# Base.net
KiCad netlist of a schematic drawn in EAGLE
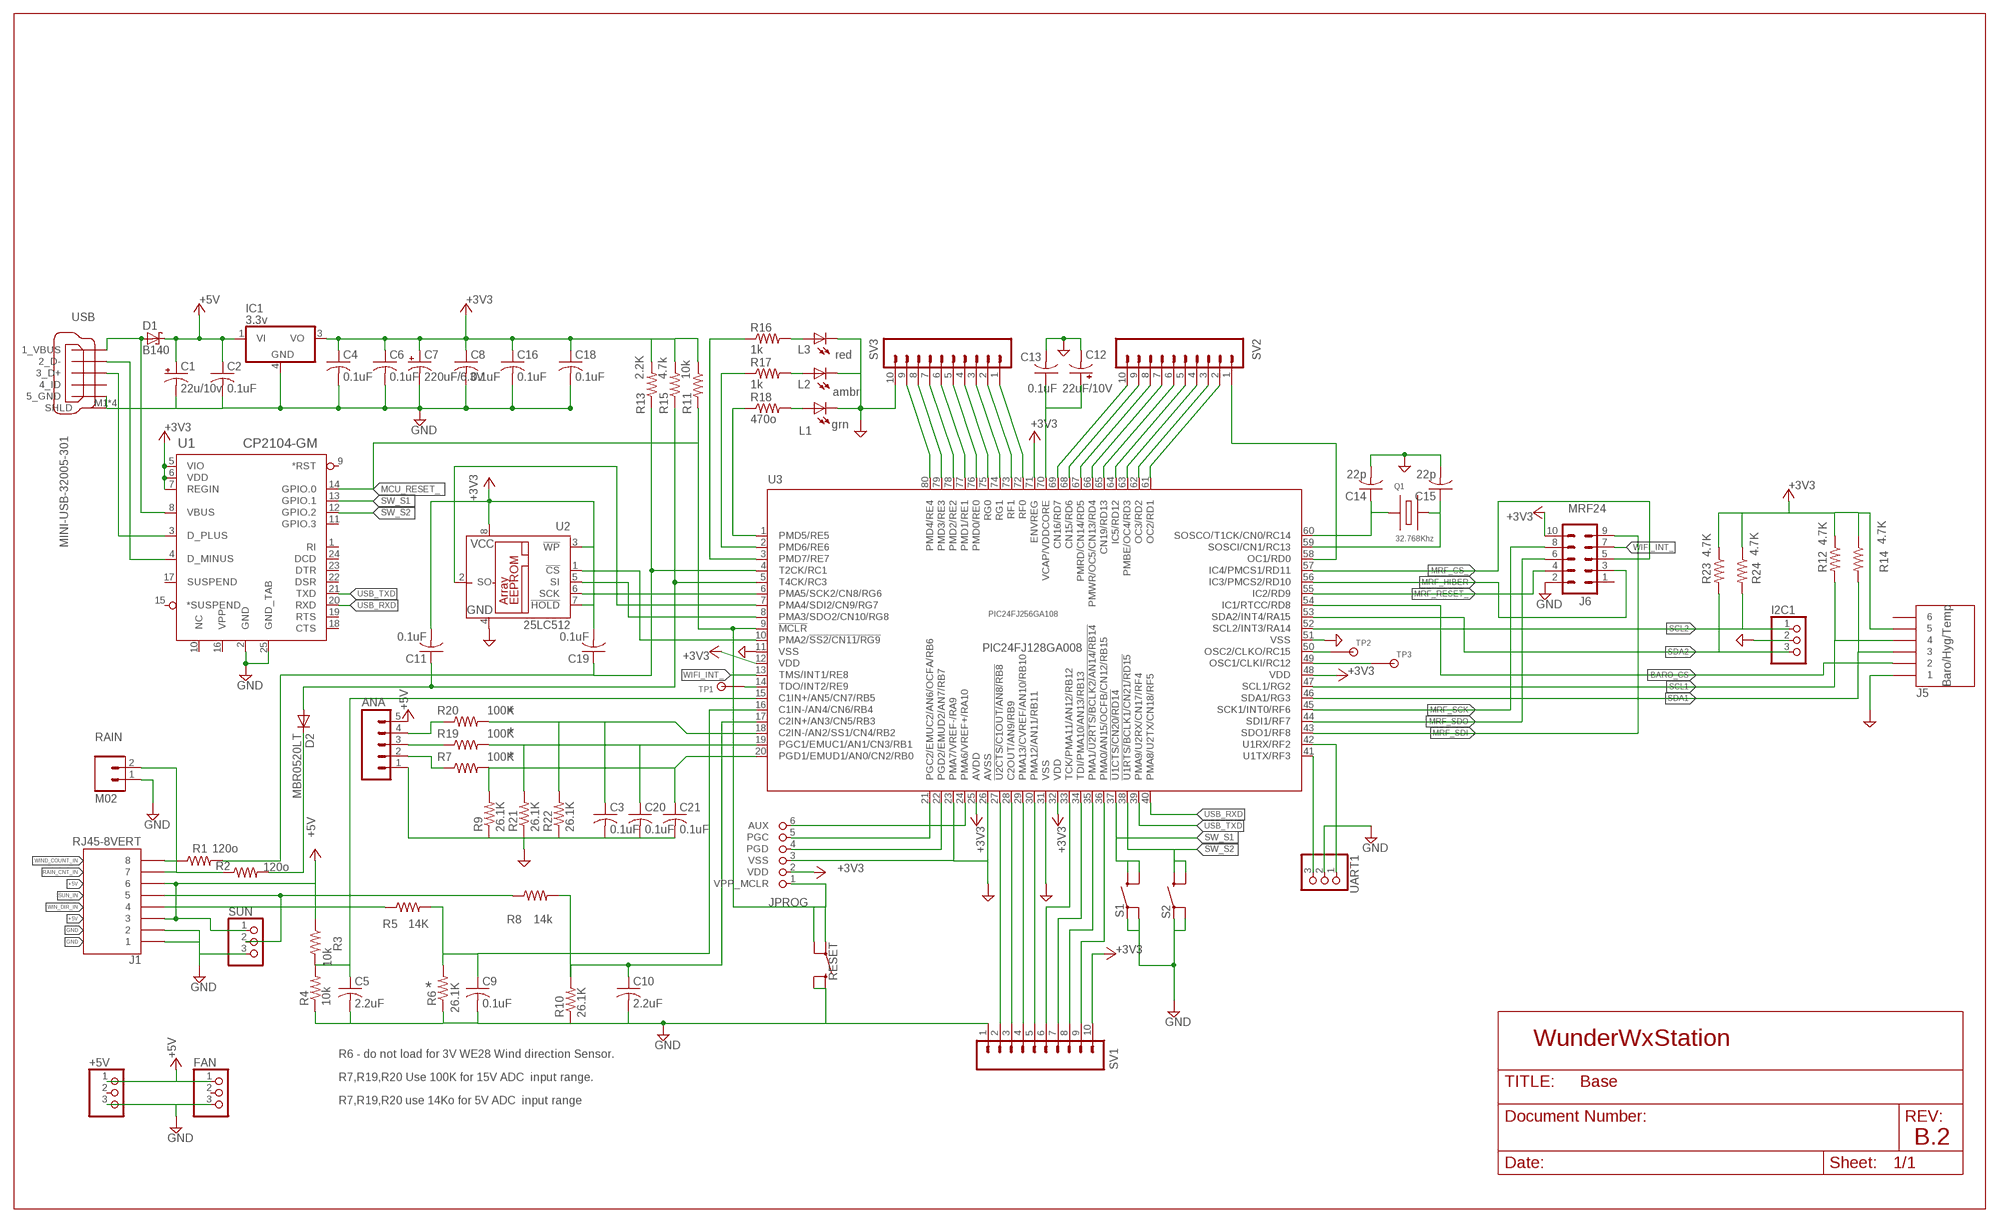
[diagram p0: schematic, sheet 1]

(export (version "E")
  (design (tool "Eeschema 10.0.6"))
  (components
    (comp (ref "+5V")
      (value "PINHD-1X3MOLEX_KK")
      (footprint "eagle-import:1X3_MOLEX_KK")
      (libsource (lib "eagle-import") (part "PINHD-1X3MOLEX_KK"))
    )
    (comp (ref "ANA")
      (value "M05PTH")
      (footprint "eagle-import:1X05")
      (libsource (lib "eagle-import") (part "M05PTH"))
    )
    (comp (ref "C1")
      (value "22u/10v")
      (footprint "eagle-import:SMC_B")
      (libsource (lib "eagle-import") (part "CPOL-USSMCB"))
    )
    (comp (ref "C2")
      (value "0.1uF")
      (footprint "eagle-import:C0805")
      (libsource (lib "eagle-import") (part "C-USC0805"))
    )
    (comp (ref "C3")
      (value "0.1uF")
      (footprint "eagle-import:C0805")
      (libsource (lib "eagle-import") (part "C-USC0805"))
    )
    (comp (ref "C4")
      (value "0.1uF")
      (footprint "eagle-import:C0805")
      (libsource (lib "eagle-import") (part "C-USC0805"))
    )
    (comp (ref "C5")
      (value "2.2uF")
      (footprint "eagle-import:C0805")
      (libsource (lib "eagle-import") (part "C-USC0805"))
    )
    (comp (ref "C6")
      (value "0.1uF")
      (footprint "eagle-import:C0805")
      (libsource (lib "eagle-import") (part "C-USC0805"))
    )
    (comp (ref "C7")
      (value "220uF/6.3V")
      (footprint "eagle-import:SMC_D")
      (libsource (lib "eagle-import") (part "CPOL-USSMCD"))
    )
    (comp (ref "C8")
      (value "0.1uF")
      (footprint "eagle-import:C0805")
      (libsource (lib "eagle-import") (part "C-USC0805"))
    )
    (comp (ref "C9")
      (value "0.1uF")
      (footprint "eagle-import:C0805")
      (libsource (lib "eagle-import") (part "C-USC0805"))
    )
    (comp (ref "C10")
      (value "2.2uF")
      (footprint "eagle-import:C0805")
      (libsource (lib "eagle-import") (part "C-USC0805"))
    )
    (comp (ref "C11")
      (value "0.1uF")
      (footprint "eagle-import:C0805")
      (libsource (lib "eagle-import") (part "C-USC0805"))
    )
    (comp (ref "C12")
      (value "22uF/10V")
      (footprint "eagle-import:SMC_B")
      (libsource (lib "eagle-import") (part "CPOL-USSMCB"))
    )
    (comp (ref "C13")
      (value "0.1uF")
      (footprint "eagle-import:C0805")
      (libsource (lib "eagle-import") (part "C-USC0805"))
    )
    (comp (ref "C14")
      (value "22p")
      (footprint "eagle-import:C0603")
      (libsource (lib "eagle-import") (part "C-USC0603"))
    )
    (comp (ref "C15")
      (value "22p")
      (footprint "eagle-import:C0603")
      (libsource (lib "eagle-import") (part "C-USC0603"))
    )
    (comp (ref "C16")
      (value "0.1uF")
      (footprint "eagle-import:C0805")
      (libsource (lib "eagle-import") (part "C-USC0805"))
    )
    (comp (ref "C18")
      (value "0.1uF")
      (footprint "eagle-import:C0805")
      (libsource (lib "eagle-import") (part "C-USC0805"))
    )
    (comp (ref "C19")
      (value "0.1uF")
      (footprint "eagle-import:C0805")
      (libsource (lib "eagle-import") (part "C-USC0805"))
    )
    (comp (ref "C20")
      (value "0.1uF")
      (footprint "eagle-import:C0805")
      (libsource (lib "eagle-import") (part "C-USC0805"))
    )
    (comp (ref "C21")
      (value "0.1uF")
      (footprint "eagle-import:C0805")
      (libsource (lib "eagle-import") (part "C-USC0805"))
    )
    (comp (ref "D1")
      (value "B140")
      (footprint "eagle-import:SMB")
      (libsource (lib "eagle-import") (part "SCHOTTKY-DIODESMD"))
    )
    (comp (ref "D2")
      (value "MBR0520LT")
      (footprint "eagle-import:SOD123")
      (libsource (lib "eagle-import") (part "MBR0520LT"))
    )
    (comp (ref "FAN")
      (value "PINHD-1X3MOLEX_KK")
      (footprint "eagle-import:1X3_MOLEX_KK")
      (libsource (lib "eagle-import") (part "PINHD-1X3MOLEX_KK"))
    )
    (comp (ref "I2C1")
      (value "PINHD-1X3")
      (footprint "eagle-import:1X03")
      (libsource (lib "eagle-import") (part "PINHD-1X3"))
    )
    (comp (ref "IC1")
      (value "3.3v")
      (footprint "eagle-import:DPACK")
      (libsource (lib "eagle-import") (part "78MXXL"))
    )
    (comp (ref "J1")
      (value "RJ45-8VERT")
      (footprint "eagle-import:RJ45_VERT")
      (libsource (lib "eagle-import") (part "RJ45-8VERT"))
    )
    (comp (ref "J5")
      (value "RJ11-6VERT_LP")
      (footprint "eagle-import:RJ11-6-VERT")
      (libsource (lib "eagle-import") (part "RJ11-6VERT_LP"))
    )
    (comp (ref "J6")
      (value "M05X22X5FE")
      (footprint "eagle-import:2X5FEMALE")
      (libsource (lib "eagle-import") (part "M05X22X5FE"))
    )
    (comp (ref "JPROG")
      (value "PIKIT2_PRG")
      (footprint "eagle-import:1X06_PIKIT")
      (libsource (lib "eagle-import") (part "PIKIT2_PRG"))
    )
    (comp (ref "L1")
      (value "grn")
      (footprint "eagle-import:CHIP-LED0603")
      (libsource (lib "eagle-import") (part "LEDCHIP-LED0603"))
    )
    (comp (ref "L2")
      (value "ambr")
      (footprint "eagle-import:CHIP-LED0603")
      (libsource (lib "eagle-import") (part "LEDCHIP-LED0603"))
    )
    (comp (ref "L3")
      (value "red")
      (footprint "eagle-import:CHIP-LED0603")
      (libsource (lib "eagle-import") (part "LEDCHIP-LED0603"))
    )
    (comp (ref "Q1")
      (value "32.768Khz")
      (footprint "eagle-import:CRYSTAL32_SMT")
      (libsource (lib "eagle-import") (part "CRYSTAL"))
    )
    (comp (ref "R1")
      (value "120o")
      (footprint "eagle-import:R0603")
      (libsource (lib "eagle-import") (part "R-US_R0603"))
    )
    (comp (ref "R2")
      (value "120o")
      (footprint "eagle-import:R0603")
      (libsource (lib "eagle-import") (part "R-US_R0603"))
    )
    (comp (ref "R3")
      (value "10k")
      (footprint "eagle-import:R0603")
      (libsource (lib "eagle-import") (part "R-US_R0603"))
    )
    (comp (ref "R4")
      (value "10k")
      (footprint "eagle-import:R0603")
      (libsource (lib "eagle-import") (part "R-US_R0603"))
    )
    (comp (ref "R5")
      (value "14K")
      (footprint "eagle-import:R0603")
      (libsource (lib "eagle-import") (part "R-US_R0603"))
    )
    (comp (ref "R6")
      (value "26.1K")
      (footprint "eagle-import:R0603")
      (libsource (lib "eagle-import") (part "R-US_R0603"))
    )
    (comp (ref "R7")
      (value "100K")
      (footprint "eagle-import:R0603")
      (libsource (lib "eagle-import") (part "R-US_R0603"))
    )
    (comp (ref "R8")
      (value "14k")
      (footprint "eagle-import:R0603")
      (libsource (lib "eagle-import") (part "R-US_R0603"))
    )
    (comp (ref "R9")
      (value "26.1K")
      (footprint "eagle-import:R0603")
      (libsource (lib "eagle-import") (part "R-US_R0603"))
    )
    (comp (ref "R10")
      (value "26.1K")
      (footprint "eagle-import:R0603")
      (libsource (lib "eagle-import") (part "R-US_R0603"))
    )
    (comp (ref "R11")
      (value "10k")
      (footprint "eagle-import:R0603")
      (libsource (lib "eagle-import") (part "R-US_R0603"))
    )
    (comp (ref "R12")
      (value "4.7K")
      (footprint "eagle-import:R0603")
      (libsource (lib "eagle-import") (part "R-US_R0603"))
    )
    (comp (ref "R13")
      (value "2.2K")
      (footprint "eagle-import:R0603")
      (libsource (lib "eagle-import") (part "R-US_R0603"))
    )
    (comp (ref "R14")
      (value "4.7K")
      (footprint "eagle-import:R0603")
      (libsource (lib "eagle-import") (part "R-US_R0603"))
    )
    (comp (ref "R15")
      (value "4.7k")
      (footprint "eagle-import:R0603")
      (libsource (lib "eagle-import") (part "R-US_R0603"))
    )
    (comp (ref "R16")
      (value "1k")
      (footprint "eagle-import:R0603")
      (libsource (lib "eagle-import") (part "R-US_R0603"))
    )
    (comp (ref "R17")
      (value "1k")
      (footprint "eagle-import:R0603")
      (libsource (lib "eagle-import") (part "R-US_R0603"))
    )
    (comp (ref "R18")
      (value "470o")
      (footprint "eagle-import:R0603")
      (libsource (lib "eagle-import") (part "R-US_R0603"))
    )
    (comp (ref "R19")
      (value "100K")
      (footprint "eagle-import:R0603")
      (libsource (lib "eagle-import") (part "R-US_R0603"))
    )
    (comp (ref "R20")
      (value "100K")
      (footprint "eagle-import:R0603")
      (libsource (lib "eagle-import") (part "R-US_R0603"))
    )
    (comp (ref "R21")
      (value "26.1K")
      (footprint "eagle-import:R0603")
      (libsource (lib "eagle-import") (part "R-US_R0603"))
    )
    (comp (ref "R22")
      (value "26.1K")
      (footprint "eagle-import:R0603")
      (libsource (lib "eagle-import") (part "R-US_R0603"))
    )
    (comp (ref "R23")
      (value "4.7K")
      (footprint "eagle-import:R0603")
      (libsource (lib "eagle-import") (part "R-US_R0603"))
    )
    (comp (ref "R24")
      (value "4.7K")
      (footprint "eagle-import:R0603")
      (libsource (lib "eagle-import") (part "R-US_R0603"))
    )
    (comp (ref "RAIN")
      (value "M02")
      (footprint "eagle-import:1X02")
      (libsource (lib "eagle-import") (part "M02"))
    )
    (comp (ref "RESET")
      (value "SWITCH-MOMENTARY-2SMD")
      (footprint "eagle-import:TACTILE_SWITCH_SMD")
      (libsource (lib "eagle-import") (part "SWITCH-MOMENTARY-2SMD"))
    )
    (comp (ref "S1")
      (value "SWITCH-MOMENTARY-2SMD")
      (footprint "eagle-import:TACTILE_SWITCH_SMD")
      (libsource (lib "eagle-import") (part "SWITCH-MOMENTARY-2SMD"))
    )
    (comp (ref "S2")
      (value "SWITCH-MOMENTARY-2SMD")
      (footprint "eagle-import:TACTILE_SWITCH_SMD")
      (libsource (lib "eagle-import") (part "SWITCH-MOMENTARY-2SMD"))
    )
    (comp (ref "SUN")
      (value "PINHD-1X3MOLEX_KK")
      (footprint "eagle-import:1X3_MOLEX_KK")
      (libsource (lib "eagle-import") (part "PINHD-1X3MOLEX_KK"))
    )
    (comp (ref "SV1")
      (value "M10\"")
      (footprint "eagle-import:1X10")
      (libsource (lib "eagle-import") (part "M10{dblquote}"))
    )
    (comp (ref "SV2")
      (value "M10\"")
      (footprint "eagle-import:1X10")
      (libsource (lib "eagle-import") (part "M10{dblquote}"))
    )
    (comp (ref "SV3")
      (value "M10\"")
      (footprint "eagle-import:1X10")
      (libsource (lib "eagle-import") (part "M10{dblquote}"))
    )
    (comp (ref "TP1")
      (value "TP10R")
      (footprint "eagle-import:TP10R")
      (libsource (lib "eagle-import") (part "TP10R"))
    )
    (comp (ref "TP2")
      (value "TP6R")
      (footprint "eagle-import:TP06R")
      (libsource (lib "eagle-import") (part "TP6R"))
    )
    (comp (ref "TP3")
      (value "TP6R")
      (footprint "eagle-import:TP06R")
      (libsource (lib "eagle-import") (part "TP6R"))
    )
    (comp (ref "U1")
      (value "CP2104-GM")
      (footprint "eagle-import:QFN24_4X4")
      (libsource (lib "eagle-import") (part "CP2104-GM"))
    )
    (comp (ref "U2")
      (value "25LC512")
      (footprint "eagle-import:SO-08")
      (fields (field (name "MF") "MICROCHIP") (field (name "MPN") "25LC080/SN"))
      (libsource (lib "eagle-import") (part "25SNLC080"))
    )
    (comp (ref "U3")
      (value "PIC24FJ128GA008")
      (footprint "eagle-import:TQFP80-12X12")
      (fields (field (name "MF") "MICROCHIP") (field (name "MPN") "PIC24FJ128GA008-I/PT"))
      (libsource (lib "eagle-import") (part "PIC24FJGA008128"))
    )
    (comp (ref "UART1")
      (value "PINHD-1X3")
      (footprint "eagle-import:1X03")
      (libsource (lib "eagle-import") (part "PINHD-1X3"))
    )
    (comp (ref "USB")
      (value "MINI-USB-32005-301")
      (footprint "eagle-import:32005-301")
      (libsource (lib "eagle-import") (part "MINI-USB-32005-301"))
    )
  )
  (nets
    (net (code "1") (name "+3V3") (class "Default")
      (node (ref "C11") (pin "2") (pinfunction "2_2") (pintype "passive"))
      (node (ref "C16") (pin "1") (pinfunction "1_1") (pintype "passive"))
      (node (ref "C18") (pin "1") (pinfunction "1_1") (pintype "passive"))
      (node (ref "C19") (pin "2") (pinfunction "2_2") (pintype "passive"))
      (node (ref "C4") (pin "1") (pinfunction "1_1") (pintype "passive"))
      (node (ref "C6") (pin "1") (pinfunction "1_1") (pintype "passive"))
      (node (ref "C7") (pin "+") (pinfunction "+_+") (pintype "passive"))
      (node (ref "C8") (pin "1") (pinfunction "1_1") (pintype "passive"))
      (node (ref "IC1") (pin "3") (pinfunction "VO_3") (pintype "passive"))
      (node (ref "J5") (pin "P$5") (pinfunction "5_P$5") (pintype "bidirectional"))
      (node (ref "J6") (pin "10") (pinfunction "10_10") (pintype "passive"))
      (node (ref "JPROG") (pin "2") (pinfunction "VDD_2") (pintype "passive"))
      (node (ref "R11") (pin "1") (pinfunction "1_1") (pintype "passive"))
      (node (ref "R12") (pin "1") (pinfunction "1_1") (pintype "passive"))
      (node (ref "R13") (pin "2") (pinfunction "2_2") (pintype "passive"))
      (node (ref "R14") (pin "1") (pinfunction "1_1") (pintype "passive"))
      (node (ref "R15") (pin "2") (pinfunction "2_2") (pintype "passive"))
      (node (ref "R23") (pin "1") (pinfunction "1_1") (pintype "passive"))
      (node (ref "R24") (pin "1") (pinfunction "1_1") (pintype "passive"))
      (node (ref "SV1") (pin "10") (pinfunction "10_10") (pintype "passive"))
      (node (ref "U1") (pin "5") (pinfunction "VIO_5") (pintype "power_in"))
      (node (ref "U1") (pin "6") (pinfunction "VDD_6") (pintype "power_in"))
      (node (ref "U1") (pin "7") (pinfunction "REGIN_7") (pintype "input"))
      (node (ref "U2") (pin "3") (pinfunction "~{WP}_3") (pintype "input"))
      (node (ref "U2") (pin "7") (pinfunction "~{HOLD}_7") (pintype "input"))
      (node (ref "U2") (pin "8") (pinfunction "VCC_8") (pintype "power_in"))
      (node (ref "U3") (pin "12") (pinfunction "VDD_12") (pintype "power_in"))
      (node (ref "U3") (pin "25") (pinfunction "AVDD_25") (pintype "power_in"))
      (node (ref "U3") (pin "32") (pinfunction "VDD_32") (pintype "power_in"))
      (node (ref "U3") (pin "48") (pinfunction "VDD_48") (pintype "power_in"))
      (node (ref "U3") (pin "71") (pinfunction "ENVREG_71") (pintype "bidirectional"))
    )
    (net (code "2") (name "+5V") (class "Default")
      (node (ref "+5V") (pin "1") (pinfunction "1_1") (pintype "passive"))
      (node (ref "ANA") (pin "5") (pinfunction "5_5") (pintype "passive"))
      (node (ref "C1") (pin "+") (pinfunction "+_+") (pintype "passive"))
      (node (ref "C2") (pin "1") (pinfunction "1_1") (pintype "passive"))
      (node (ref "D1") (pin "C") (pinfunction "C_C") (pintype "passive"))
      (node (ref "FAN") (pin "1") (pinfunction "1_1") (pintype "passive"))
      (node (ref "IC1") (pin "1") (pinfunction "VI_1") (pintype "input"))
      (node (ref "J1") (pin "P$3") (pinfunction "3_P$3") (pintype "bidirectional"))
      (node (ref "J1") (pin "P$6") (pinfunction "6_P$6") (pintype "bidirectional"))
      (node (ref "R3") (pin "1") (pinfunction "1_1") (pintype "passive"))
      (node (ref "SUN") (pin "1") (pinfunction "1_1") (pintype "passive"))
    )
    (net (code "3") (name "BARO_CS") (class "Default")
      (node (ref "J5") (pin "P$2") (pinfunction "2_P$2") (pintype "bidirectional"))
      (node (ref "U3") (pin "54") (pinfunction "IC1/RTCC/RD8_54") (pintype "bidirectional"))
    )
    (net (code "4") (name "GND") (class "Default")
      (node (ref "+5V") (pin "3") (pinfunction "3_3") (pintype "passive"))
      (node (ref "ANA") (pin "1") (pinfunction "1_1") (pintype "passive"))
      (node (ref "C1") (pin "-") (pinfunction "-_-") (pintype "passive"))
      (node (ref "C10") (pin "2") (pinfunction "2_2") (pintype "passive"))
      (node (ref "C12") (pin "-") (pinfunction "-_-") (pintype "passive"))
      (node (ref "C13") (pin "2") (pinfunction "2_2") (pintype "passive"))
      (node (ref "C14") (pin "2") (pinfunction "2_2") (pintype "passive"))
      (node (ref "C15") (pin "2") (pinfunction "2_2") (pintype "passive"))
      (node (ref "C16") (pin "2") (pinfunction "2_2") (pintype "passive"))
      (node (ref "C18") (pin "2") (pinfunction "2_2") (pintype "passive"))
      (node (ref "C2") (pin "2") (pinfunction "2_2") (pintype "passive"))
      (node (ref "C20") (pin "2") (pinfunction "2_2") (pintype "passive"))
      (node (ref "C21") (pin "2") (pinfunction "2_2") (pintype "passive"))
      (node (ref "C3") (pin "2") (pinfunction "2_2") (pintype "passive"))
      (node (ref "C4") (pin "2") (pinfunction "2_2") (pintype "passive"))
      (node (ref "C5") (pin "2") (pinfunction "2_2") (pintype "passive"))
      (node (ref "C6") (pin "2") (pinfunction "2_2") (pintype "passive"))
      (node (ref "C7") (pin "-") (pinfunction "-_-") (pintype "passive"))
      (node (ref "C8") (pin "2") (pinfunction "2_2") (pintype "passive"))
      (node (ref "C9") (pin "2") (pinfunction "2_2") (pintype "passive"))
      (node (ref "FAN") (pin "3") (pinfunction "3_3") (pintype "passive"))
      (node (ref "I2C1") (pin "2") (pinfunction "2_2") (pintype "passive"))
      (node (ref "IC1") (pin "4") (pinfunction "GND_4") (pintype "passive"))
      (node (ref "J1") (pin "P$1") (pinfunction "1_P$1") (pintype "bidirectional"))
      (node (ref "J1") (pin "P$2") (pinfunction "2_P$2") (pintype "bidirectional"))
      (node (ref "J5") (pin "P$1") (pinfunction "1_P$1") (pintype "bidirectional"))
      (node (ref "J6") (pin "2") (pinfunction "2_2") (pintype "passive"))
      (node (ref "JPROG") (pin "3") (pinfunction "VSS_3") (pintype "passive"))
      (node (ref "L1") (pin "C") (pinfunction "C_C") (pintype "passive"))
      (node (ref "L2") (pin "C") (pinfunction "C_C") (pintype "passive"))
      (node (ref "L3") (pin "C") (pinfunction "C_C") (pintype "passive"))
      (node (ref "R10") (pin "1") (pinfunction "1_1") (pintype "passive"))
      (node (ref "R21") (pin "1") (pinfunction "1_1") (pintype "passive"))
      (node (ref "R22") (pin "1") (pinfunction "1_1") (pintype "passive"))
      (node (ref "R4") (pin "1") (pinfunction "1_1") (pintype "passive"))
      (node (ref "R6") (pin "1") (pinfunction "1_1") (pintype "passive"))
      (node (ref "R9") (pin "1") (pinfunction "1_1") (pintype "passive"))
      (node (ref "RAIN") (pin "1") (pinfunction "1_1") (pintype "passive"))
      (node (ref "RESET") (pin "3") (pinfunction "2_3") (pintype "passive"))
      (node (ref "RESET") (pin "4") (pinfunction "3_4") (pintype "passive"))
      (node (ref "S1") (pin "1") (pinfunction "1_1") (pintype "passive"))
      (node (ref "S1") (pin "2") (pinfunction "4_2") (pintype "passive"))
      (node (ref "S2") (pin "1") (pinfunction "1_1") (pintype "passive"))
      (node (ref "S2") (pin "2") (pinfunction "4_2") (pintype "passive"))
      (node (ref "SUN") (pin "3") (pinfunction "3_3") (pintype "passive"))
      (node (ref "SV1") (pin "1") (pinfunction "1_1") (pintype "passive"))
      (node (ref "SV3") (pin "10") (pinfunction "10_10") (pintype "passive"))
      (node (ref "U1") (pin "2") (pinfunction "GND_2") (pintype "power_in"))
      (node (ref "U1") (pin "25") (pinfunction "GND_TAB_25") (pintype "passive"))
      (node (ref "U2") (pin "4") (pinfunction "GND_4") (pintype "power_in"))
      (node (ref "U3") (pin "11") (pinfunction "VSS_11") (pintype "power_in"))
      (node (ref "U3") (pin "23") (pinfunction "PMA7/VREF-/RA9_23") (pintype "bidirectional"))
      (node (ref "U3") (pin "26") (pinfunction "AVSS_26") (pintype "power_in"))
      (node (ref "U3") (pin "31") (pinfunction "VSS_31") (pintype "power_in"))
      (node (ref "U3") (pin "51") (pinfunction "VSS_51") (pintype "power_in"))
      (node (ref "UART1") (pin "2") (pinfunction "2_2") (pintype "passive"))
      (node (ref "USB") (pin "5_USB_GND") (pinfunction "5_GND_5_USB_GND") (pintype "passive"))
      (node (ref "USB") (pin "M1") (pinfunction "SHLD_M1") (pintype "passive"))
      (node (ref "USB") (pin "M2") (pinfunction "SHLD_M2") (pintype "passive"))
      (node (ref "USB") (pin "M3") (pinfunction "SHLD_M3") (pintype "passive"))
      (node (ref "USB") (pin "M4") (pinfunction "SHLD_M4") (pintype "passive"))
    )
    (net (code "5") (name "MCU_RESET_") (class "Default")
      (node (ref "JPROG") (pin "1") (pinfunction "VPP_MCLR_1") (pintype "passive"))
      (node (ref "R11") (pin "2") (pinfunction "2_2") (pintype "passive"))
      (node (ref "RESET") (pin "1") (pinfunction "1_1") (pintype "passive"))
      (node (ref "RESET") (pin "2") (pinfunction "4_2") (pintype "passive"))
      (node (ref "U1") (pin "14") (pinfunction "GPIO.0_14") (pintype "passive"))
      (node (ref "U3") (pin "9") (pinfunction "~{MCLR}_9") (pintype "bidirectional"))
    )
    (net (code "6") (name "MRF_CS_") (class "Default")
      (node (ref "J6") (pin "5") (pinfunction "5_5") (pintype "passive"))
      (node (ref "U3") (pin "57") (pinfunction "IC4/PMCS1/RD11_57") (pintype "bidirectional"))
    )
    (net (code "7") (name "MRF_HIBER") (class "Default")
      (node (ref "J6") (pin "3") (pinfunction "3_3") (pintype "passive"))
      (node (ref "U3") (pin "56") (pinfunction "IC3/PMCS2/RD10_56") (pintype "bidirectional"))
    )
    (net (code "8") (name "MRF_RESET_") (class "Default")
      (node (ref "J6") (pin "4") (pinfunction "4_4") (pintype "passive"))
      (node (ref "U3") (pin "55") (pinfunction "IC2/RD9_55") (pintype "bidirectional"))
    )
    (net (code "9") (name "MRF_SCK") (class "Default")
      (node (ref "J6") (pin "8") (pinfunction "8_8") (pintype "passive"))
      (node (ref "U3") (pin "45") (pinfunction "SCK1/INT0/RF6_45") (pintype "bidirectional"))
    )
    (net (code "10") (name "MRF_SDI") (class "Default")
      (node (ref "J6") (pin "9") (pinfunction "9_9") (pintype "passive"))
      (node (ref "U3") (pin "43") (pinfunction "SDO1/RF8_43") (pintype "bidirectional"))
    )
    (net (code "11") (name "MRF_SDO") (class "Default")
      (node (ref "J6") (pin "6") (pinfunction "6_6") (pintype "passive"))
      (node (ref "U3") (pin "44") (pinfunction "SDI1/RF7_44") (pintype "bidirectional"))
    )
    (net (code "12") (name "Net-(ANA-Pad2)") (class "Default")
      (node (ref "ANA") (pin "2") (pinfunction "2_2") (pintype "passive"))
      (node (ref "R7") (pin "1") (pinfunction "1_1") (pintype "passive"))
    )
    (net (code "13") (name "Net-(ANA-Pad3)") (class "Default")
      (node (ref "ANA") (pin "3") (pinfunction "3_3") (pintype "passive"))
      (node (ref "R19") (pin "1") (pinfunction "1_1") (pintype "passive"))
    )
    (net (code "14") (name "Net-(ANA-Pad4)") (class "Default")
      (node (ref "ANA") (pin "4") (pinfunction "4_4") (pintype "passive"))
      (node (ref "R20") (pin "1") (pinfunction "1_1") (pintype "passive"))
    )
    (net (code "15") (name "Net-(D2-PadC)") (class "Default")
      (node (ref "D2") (pin "C") (pinfunction "C_C") (pintype "passive"))
      (node (ref "R2") (pin "2") (pinfunction "2_2") (pintype "passive"))
    )
    (net (code "16") (name "Net-(JPROG-AUX)") (class "Default")
      (node (ref "JPROG") (pin "6") (pinfunction "AUX_6") (pintype "passive"))
      (node (ref "U3") (pin "24") (pinfunction "PMA6/VREF+/RA10_24") (pintype "bidirectional"))
    )
    (net (code "17") (name "Net-(JPROG-PGC)") (class "Default")
      (node (ref "JPROG") (pin "5") (pinfunction "PGC_5") (pintype "passive"))
      (node (ref "U3") (pin "21") (pinfunction "PGC2/EMUC2/AN6/OCFA/RB6_21") (pintype "bidirectional"))
    )
    (net (code "18") (name "Net-(JPROG-PGD)") (class "Default")
      (node (ref "JPROG") (pin "4") (pinfunction "PGD_4") (pintype "passive"))
      (node (ref "U3") (pin "22") (pinfunction "PGD2/EMUD2/AN7/RB7_22") (pintype "bidirectional"))
    )
    (net (code "19") (name "Net-(L1-PadA)") (class "Default")
      (node (ref "L1") (pin "A") (pinfunction "A_A") (pintype "passive"))
      (node (ref "R18") (pin "2") (pinfunction "2_2") (pintype "passive"))
    )
    (net (code "20") (name "Net-(L2-PadA)") (class "Default")
      (node (ref "L2") (pin "A") (pinfunction "A_A") (pintype "passive"))
      (node (ref "R17") (pin "2") (pinfunction "2_2") (pintype "passive"))
    )
    (net (code "21") (name "Net-(L3-PadA)") (class "Default")
      (node (ref "L3") (pin "A") (pinfunction "A_A") (pintype "passive"))
      (node (ref "R16") (pin "2") (pinfunction "2_2") (pintype "passive"))
    )
    (net (code "22") (name "Net-(Q1-P$1)") (class "Default")
      (node (ref "C14") (pin "1") (pinfunction "1_1") (pintype "passive"))
      (node (ref "Q1") (pin "P$2") (pinfunction "P$1_P$2") (pintype "bidirectional"))
      (node (ref "U3") (pin "60") (pinfunction "SOSCO/T1CK/CN0/RC14_60") (pintype "bidirectional"))
    )
    (net (code "23") (name "Net-(Q1-P$2)") (class "Default")
      (node (ref "C15") (pin "1") (pinfunction "1_1") (pintype "passive"))
      (node (ref "Q1") (pin "P$3") (pinfunction "P$2_P$3") (pintype "bidirectional"))
      (node (ref "U3") (pin "59") (pinfunction "SOSCI/CN1/RC13_59") (pintype "bidirectional"))
    )
    (net (code "24") (name "Net-(TP1-P$1)") (class "Default")
      (node (ref "TP1") (pin "TP_1") (pinfunction "P$1_TP_1") (pintype "bidirectional"))
      (node (ref "U3") (pin "14") (pinfunction "TDO/INT2/RE9_14") (pintype "bidirectional"))
    )
    (net (code "25") (name "Net-(TP2-P$1)") (class "Default")
      (node (ref "TP2") (pin "TP_1") (pinfunction "P$1_TP_1") (pintype "bidirectional"))
      (node (ref "U3") (pin "50") (pinfunction "OSC2/CLKO/RC15_50") (pintype "bidirectional"))
    )
    (net (code "26") (name "Net-(TP3-P$1)") (class "Default")
      (node (ref "TP3") (pin "TP_1") (pinfunction "P$1_TP_1") (pintype "bidirectional"))
      (node (ref "U3") (pin "49") (pinfunction "OSC1/CLKI/RC12_49") (pintype "bidirectional"))
    )
    (net (code "27") (name "Net-(U1-D_MINUS)") (class "Default")
      (node (ref "U1") (pin "4") (pinfunction "D_MINUS_4") (pintype "passive"))
      (node (ref "USB") (pin "2_D-") (pinfunction "2_D-_2_D-") (pintype "passive"))
    )
    (net (code "28") (name "Net-(U1-D_PLUS)") (class "Default")
      (node (ref "U1") (pin "3") (pinfunction "D_PLUS_3") (pintype "passive"))
      (node (ref "USB") (pin "3_D+") (pinfunction "3_D+_3_D+") (pintype "passive"))
    )
    (net (code "29") (name "Net-(U1-VBUS)") (class "Default")
      (node (ref "D1") (pin "A") (pinfunction "A_A") (pintype "passive"))
      (node (ref "U1") (pin "8") (pinfunction "VBUS_8") (pintype "input"))
      (node (ref "USB") (pin "1_VBUS") (pinfunction "1_VBUS_1_VBUS") (pintype "passive"))
    )
    (net (code "30") (name "Net-(U2-SCK)") (class "Default")
      (node (ref "U2") (pin "6") (pinfunction "SCK_6") (pintype "input"))
      (node (ref "U3") (pin "6") (pinfunction "PMA5/SCK2/CN8/RG6_6") (pintype "bidirectional"))
    )
    (net (code "31") (name "Net-(U2-SI)") (class "Default")
      (node (ref "U2") (pin "5") (pinfunction "SI_5") (pintype "input"))
      (node (ref "U3") (pin "8") (pinfunction "PMA3/SDO2/CN10/RG8_8") (pintype "bidirectional"))
    )
    (net (code "32") (name "Net-(U2-SO)") (class "Default")
      (node (ref "U2") (pin "2") (pinfunction "SO_2") (pintype "bidirectional"))
      (node (ref "U3") (pin "7") (pinfunction "PMA4/SDI2/CN9/RG7_7") (pintype "bidirectional"))
    )
    (net (code "33") (name "Net-(U2-~{CS})") (class "Default")
      (node (ref "U2") (pin "1") (pinfunction "~{CS}_1") (pintype "input"))
      (node (ref "U3") (pin "10") (pinfunction "PMA2/~{SS2/CN11/RG9}_10") (pintype "bidirectional"))
    )
    (net (code "34") (name "Net-(U3-C1IN+{slash}AN5{slash}CN7{slash}RB5)") (class "Default")
      (node (ref "C5") (pin "1") (pinfunction "1_1") (pintype "passive"))
      (node (ref "R3") (pin "2") (pinfunction "2_2") (pintype "passive"))
      (node (ref "R4") (pin "2") (pinfunction "2_2") (pintype "passive"))
      (node (ref "U3") (pin "15") (pinfunction "C1IN+/AN5/CN7/RB5_15") (pintype "bidirectional"))
    )
    (net (code "35") (name "Net-(U3-C1IN-{slash}AN4{slash}CN6{slash}RB4)") (class "Default")
      (node (ref "C9") (pin "1") (pinfunction "1_1") (pintype "passive"))
      (node (ref "R5") (pin "2") (pinfunction "2_2") (pintype "passive"))
      (node (ref "R6") (pin "2") (pinfunction "2_2") (pintype "passive"))
      (node (ref "U3") (pin "16") (pinfunction "C1IN-/AN4/CN6/RB4_16") (pintype "bidirectional"))
    )
    (net (code "36") (name "Net-(U3-C2IN+{slash}AN3{slash}CN5{slash}RB3)") (class "Default")
      (node (ref "C10") (pin "1") (pinfunction "1_1") (pintype "passive"))
      (node (ref "R10") (pin "2") (pinfunction "2_2") (pintype "passive"))
      (node (ref "R8") (pin "2") (pinfunction "2_2") (pintype "passive"))
      (node (ref "U3") (pin "17") (pinfunction "C2IN+/AN3/CN5/RB3_17") (pintype "bidirectional"))
    )
    (net (code "37") (name "Net-(U3-C2IN-{slash}AN2{slash}SS1{slash}CN4{slash}RB2)") (class "Default")
      (node (ref "C3") (pin "1") (pinfunction "1_1") (pintype "passive"))
      (node (ref "R20") (pin "2") (pinfunction "2_2") (pintype "passive"))
      (node (ref "R22") (pin "2") (pinfunction "2_2") (pintype "passive"))
      (node (ref "U3") (pin "18") (pinfunction "C2IN-/AN2/SS1/CN4/RB2_18") (pintype "bidirectional"))
    )
    (net (code "38") (name "Net-(U3-C2OUT{slash}AN9{slash}RB9)") (class "Default")
      (node (ref "SV1") (pin "3") (pinfunction "3_3") (pintype "passive"))
      (node (ref "U3") (pin "28") (pinfunction "C2OUT/AN9/RB9_28") (pintype "bidirectional"))
    )
    (net (code "39") (name "Net-(U3-CN15{slash}RD6)") (class "Default")
      (node (ref "SV2") (pin "9") (pinfunction "9_9") (pintype "passive"))
      (node (ref "U3") (pin "68") (pinfunction "CN15/RD6_68") (pintype "bidirectional"))
    )
    (net (code "40") (name "Net-(U3-CN16{slash}RD7)") (class "Default")
      (node (ref "SV2") (pin "10") (pinfunction "10_10") (pintype "passive"))
      (node (ref "U3") (pin "69") (pinfunction "CN16/RD7_69") (pintype "bidirectional"))
    )
    (net (code "41") (name "Net-(U3-CN19{slash}RD13)") (class "Default")
      (node (ref "SV2") (pin "6") (pinfunction "6_6") (pintype "passive"))
      (node (ref "U3") (pin "65") (pinfunction "CN19/RD13_65") (pintype "bidirectional"))
    )
    (net (code "42") (name "Net-(U3-IC5{slash}RD12)") (class "Default")
      (node (ref "SV2") (pin "5") (pinfunction "5_5") (pintype "passive"))
      (node (ref "U3") (pin "64") (pinfunction "IC5/RD12_64") (pintype "bidirectional"))
    )
    (net (code "43") (name "Net-(U3-OC1{slash}RD0)") (class "Default")
      (node (ref "SV2") (pin "1") (pinfunction "1_1") (pintype "passive"))
      (node (ref "U3") (pin "58") (pinfunction "OC1/RD0_58") (pintype "bidirectional"))
    )
    (net (code "44") (name "Net-(U3-OC2{slash}RD1)") (class "Default")
      (node (ref "SV2") (pin "2") (pinfunction "2_2") (pintype "passive"))
      (node (ref "U3") (pin "61") (pinfunction "OC2/RD1_61") (pintype "bidirectional"))
    )
    (net (code "45") (name "Net-(U3-OC3{slash}RD2)") (class "Default")
      (node (ref "SV2") (pin "3") (pinfunction "3_3") (pintype "passive"))
      (node (ref "U3") (pin "62") (pinfunction "OC3/RD2_62") (pintype "bidirectional"))
    )
    (net (code "46") (name "Net-(U3-PGC1{slash}EMUC1{slash}AN1{slash}CN3{slash}RB1)") (class "Default")
      (node (ref "C20") (pin "1") (pinfunction "1_1") (pintype "passive"))
      (node (ref "R19") (pin "2") (pinfunction "2_2") (pintype "passive"))
      (node (ref "R21") (pin "2") (pinfunction "2_2") (pintype "passive"))
      (node (ref "U3") (pin "19") (pinfunction "PGC1/EMUC1/AN1/CN3/RB1_19") (pintype "bidirectional"))
    )
    (net (code "47") (name "Net-(U3-PGD1{slash}EMUD1{slash}AN0{slash}CN2{slash}RB0)") (class "Default")
      (node (ref "C21") (pin "1") (pinfunction "1_1") (pintype "passive"))
      (node (ref "R7") (pin "2") (pinfunction "2_2") (pintype "passive"))
      (node (ref "R9") (pin "2") (pinfunction "2_2") (pintype "passive"))
      (node (ref "U3") (pin "20") (pinfunction "PGD1/EMUD1/AN0/CN2/RB0_20") (pintype "bidirectional"))
    )
    (net (code "48") (name "Net-(U3-PMA0{slash}AN15{slash}OCFB{slash}CN12{slash}RB15)") (class "Default")
      (node (ref "SV1") (pin "9") (pinfunction "9_9") (pintype "passive"))
      (node (ref "U3") (pin "36") (pinfunction "PMA0/AN15/OCFB/CN12/RB15_36") (pintype "bidirectional"))
    )
    (net (code "49") (name "Net-(U3-PMA1{slash}~{U2RTS{slash}BCLK2{slash}AN14{slash}RB14})") (class "Default")
      (node (ref "SV1") (pin "8") (pinfunction "8_8") (pintype "passive"))
      (node (ref "U3") (pin "35") (pinfunction "PMA1/~{U2RTS/BCLK2/AN14/RB14}_35") (pintype "bidirectional"))
    )
    (net (code "50") (name "Net-(U3-PMA12{slash}AN11{slash}RB11)") (class "Default")
      (node (ref "SV1") (pin "5") (pinfunction "5_5") (pintype "passive"))
      (node (ref "U3") (pin "30") (pinfunction "PMA12/AN11/RB11_30") (pintype "bidirectional"))
    )
    (net (code "51") (name "Net-(U3-PMA13{slash}CVREF{slash}AN10{slash}RB10)") (class "Default")
      (node (ref "SV1") (pin "4") (pinfunction "4_4") (pintype "passive"))
      (node (ref "U3") (pin "29") (pinfunction "PMA13/CVREF/AN10/RB10_29") (pintype "bidirectional"))
    )
    (net (code "52") (name "Net-(U3-PMBE{slash}OC4{slash}RD3)") (class "Default")
      (node (ref "SV2") (pin "4") (pinfunction "4_4") (pintype "passive"))
      (node (ref "U3") (pin "63") (pinfunction "PMBE/OC4/RD3_63") (pintype "bidirectional"))
    )
    (net (code "53") (name "Net-(U3-PMD0{slash}RE0)") (class "Default")
      (node (ref "SV3") (pin "5") (pinfunction "5_5") (pintype "passive"))
      (node (ref "U3") (pin "76") (pinfunction "PMD0/RE0_76") (pintype "bidirectional"))
    )
    (net (code "54") (name "Net-(U3-PMD1{slash}RE1)") (class "Default")
      (node (ref "SV3") (pin "6") (pinfunction "6_6") (pintype "passive"))
      (node (ref "U3") (pin "77") (pinfunction "PMD1/RE1_77") (pintype "bidirectional"))
    )
    (net (code "55") (name "Net-(U3-PMD2{slash}RE2)") (class "Default")
      (node (ref "SV3") (pin "7") (pinfunction "7_7") (pintype "passive"))
      (node (ref "U3") (pin "78") (pinfunction "PMD2/RE2_78") (pintype "bidirectional"))
    )
    (net (code "56") (name "Net-(U3-PMD3{slash}RE3)") (class "Default")
      (node (ref "SV3") (pin "8") (pinfunction "8_8") (pintype "passive"))
      (node (ref "U3") (pin "79") (pinfunction "PMD3/RE3_79") (pintype "bidirectional"))
    )
    (net (code "57") (name "Net-(U3-PMD4{slash}RE4)") (class "Default")
      (node (ref "SV3") (pin "9") (pinfunction "9_9") (pintype "passive"))
      (node (ref "U3") (pin "80") (pinfunction "PMD4/RE4_80") (pintype "bidirectional"))
    )
    (net (code "58") (name "Net-(U3-PMD5{slash}RE5)") (class "Default")
      (node (ref "R18") (pin "1") (pinfunction "1_1") (pintype "passive"))
      (node (ref "U3") (pin "1") (pinfunction "PMD5/RE5_1") (pintype "bidirectional"))
    )
    (net (code "59") (name "Net-(U3-PMD6{slash}RE6)") (class "Default")
      (node (ref "R17") (pin "1") (pinfunction "1_1") (pintype "passive"))
      (node (ref "U3") (pin "2") (pinfunction "PMD6/RE6_2") (pintype "bidirectional"))
    )
    (net (code "60") (name "Net-(U3-PMD7{slash}RE7)") (class "Default")
      (node (ref "R16") (pin "1") (pinfunction "1_1") (pintype "passive"))
      (node (ref "U3") (pin "3") (pinfunction "PMD7/RE7_3") (pintype "bidirectional"))
    )
    (net (code "61") (name "Net-(U3-PMRD{slash}CN14{slash}RD5)") (class "Default")
      (node (ref "SV2") (pin "8") (pinfunction "8_8") (pintype "passive"))
      (node (ref "U3") (pin "67") (pinfunction "PMRD/CN14/RD5_67") (pintype "bidirectional"))
    )
    (net (code "62") (name "Net-(U3-PMWR{slash}OC5{slash}CN13{slash}RD4)") (class "Default")
      (node (ref "SV2") (pin "7") (pinfunction "7_7") (pintype "passive"))
      (node (ref "U3") (pin "66") (pinfunction "PMWR/OC5/CN13/RD4_66") (pintype "bidirectional"))
    )
    (net (code "63") (name "Net-(U3-RF0)") (class "Default")
      (node (ref "SV3") (pin "1") (pinfunction "1_1") (pintype "passive"))
      (node (ref "U3") (pin "72") (pinfunction "RF0_72") (pintype "bidirectional"))
    )
    (net (code "64") (name "Net-(U3-RF1)") (class "Default")
      (node (ref "SV3") (pin "2") (pinfunction "2_2") (pintype "passive"))
      (node (ref "U3") (pin "73") (pinfunction "RF1_73") (pintype "bidirectional"))
    )
    (net (code "65") (name "Net-(U3-RG0)") (class "Default")
      (node (ref "SV3") (pin "4") (pinfunction "4_4") (pintype "passive"))
      (node (ref "U3") (pin "75") (pinfunction "RG0_75") (pintype "bidirectional"))
    )
    (net (code "66") (name "Net-(U3-RG1)") (class "Default")
      (node (ref "SV3") (pin "3") (pinfunction "3_3") (pintype "passive"))
      (node (ref "U3") (pin "74") (pinfunction "RG1_74") (pintype "bidirectional"))
    )
    (net (code "67") (name "Net-(U3-T2CK{slash}RC1)") (class "Default")
      (node (ref "C19") (pin "1") (pinfunction "1_1") (pintype "passive"))
      (node (ref "R1") (pin "2") (pinfunction "2_2") (pintype "passive"))
      (node (ref "R13") (pin "1") (pinfunction "1_1") (pintype "passive"))
      (node (ref "U3") (pin "4") (pinfunction "T2CK/RC1_4") (pintype "bidirectional"))
    )
    (net (code "68") (name "Net-(U3-T4CK{slash}RC3)") (class "Default")
      (node (ref "C11") (pin "1") (pinfunction "1_1") (pintype "passive"))
      (node (ref "D2") (pin "A") (pinfunction "A_A") (pintype "passive"))
      (node (ref "R15") (pin "1") (pinfunction "1_1") (pintype "passive"))
      (node (ref "U3") (pin "5") (pinfunction "T4CK/RC3_5") (pintype "bidirectional"))
    )
    (net (code "69") (name "Net-(U3-TCK{slash}PMA11{slash}AN12{slash}RB12)") (class "Default")
      (node (ref "SV1") (pin "6") (pinfunction "6_6") (pintype "passive"))
      (node (ref "U3") (pin "33") (pinfunction "TCK/PMA11/AN12/RB12_33") (pintype "bidirectional"))
    )
    (net (code "70") (name "Net-(U3-TDI{slash}PMA10{slash}AN13{slash}RB13)") (class "Default")
      (node (ref "SV1") (pin "7") (pinfunction "7_7") (pintype "passive"))
      (node (ref "U3") (pin "34") (pinfunction "TDI/PMA10/AN13/RB13_34") (pintype "bidirectional"))
    )
    (net (code "71") (name "Net-(U3-U1RX{slash}RF2)") (class "Default")
      (node (ref "U3") (pin "42") (pinfunction "U1RX/RF2_42") (pintype "bidirectional"))
      (node (ref "UART1") (pin "1") (pinfunction "1_1") (pintype "passive"))
    )
    (net (code "72") (name "Net-(U3-U1TX{slash}RF3)") (class "Default")
      (node (ref "U3") (pin "41") (pinfunction "U1TX/RF3_41") (pintype "bidirectional"))
      (node (ref "UART1") (pin "3") (pinfunction "3_3") (pintype "passive"))
    )
    (net (code "73") (name "Net-(U3-VCAP{slash}VDDCORE)") (class "Default")
      (node (ref "C12") (pin "+") (pinfunction "+_+") (pintype "passive"))
      (node (ref "C13") (pin "1") (pinfunction "1_1") (pintype "passive"))
      (node (ref "U3") (pin "70") (pinfunction "VCAP/VDDCORE_70") (pintype "bidirectional"))
    )
    (net (code "74") (name "Net-(U3-~{U2CTS{slash}C1OUT{slash}AN8{slash}RB8})") (class "Default")
      (node (ref "SV1") (pin "2") (pinfunction "2_2") (pintype "passive"))
      (node (ref "U3") (pin "27") (pinfunction "~{U2CTS/C1OUT/AN8/RB8}_27") (pintype "bidirectional"))
    )
    (net (code "75") (name "RAIN_CNT_IN") (class "Default")
      (node (ref "J1") (pin "P$7") (pinfunction "7_P$7") (pintype "bidirectional"))
      (node (ref "R2") (pin "1") (pinfunction "1_1") (pintype "passive"))
      (node (ref "RAIN") (pin "2") (pinfunction "2_2") (pintype "passive"))
    )
    (net (code "76") (name "SCL1") (class "Default")
      (node (ref "J5") (pin "P$4") (pinfunction "4_P$4") (pintype "bidirectional"))
      (node (ref "R12") (pin "2") (pinfunction "2_2") (pintype "passive"))
      (node (ref "U3") (pin "47") (pinfunction "SCL1/RG2_47") (pintype "bidirectional"))
    )
    (net (code "77") (name "SCL2") (class "Default")
      (node (ref "I2C1") (pin "1") (pinfunction "1_1") (pintype "passive"))
      (node (ref "R24") (pin "2") (pinfunction "2_2") (pintype "passive"))
      (node (ref "U3") (pin "52") (pinfunction "SCL2/INT3/RA14_52") (pintype "bidirectional"))
    )
    (net (code "78") (name "SDA1") (class "Default")
      (node (ref "J5") (pin "P$3") (pinfunction "3_P$3") (pintype "bidirectional"))
      (node (ref "R14") (pin "2") (pinfunction "2_2") (pintype "passive"))
      (node (ref "U3") (pin "46") (pinfunction "SDA1/RG3_46") (pintype "bidirectional"))
    )
    (net (code "79") (name "SDA2") (class "Default")
      (node (ref "I2C1") (pin "3") (pinfunction "3_3") (pintype "passive"))
      (node (ref "R23") (pin "2") (pinfunction "2_2") (pintype "passive"))
      (node (ref "U3") (pin "53") (pinfunction "SDA2/INT4/RA15_53") (pintype "bidirectional"))
    )
    (net (code "80") (name "SUN_IN") (class "Default")
      (node (ref "J1") (pin "P$5") (pinfunction "5_P$5") (pintype "bidirectional"))
      (node (ref "R8") (pin "1") (pinfunction "1_1") (pintype "passive"))
      (node (ref "SUN") (pin "2") (pinfunction "2_2") (pintype "passive"))
    )
    (net (code "81") (name "SW_S1") (class "Default")
      (node (ref "S1") (pin "3") (pinfunction "2_3") (pintype "passive"))
      (node (ref "S1") (pin "4") (pinfunction "3_4") (pintype "passive"))
      (node (ref "U1") (pin "13") (pinfunction "GPIO.1_13") (pintype "passive"))
      (node (ref "U3") (pin "37") (pinfunction "~{U1CTS/CN20/RD14}_37") (pintype "bidirectional"))
    )
    (net (code "82") (name "SW_S2") (class "Default")
      (node (ref "S2") (pin "3") (pinfunction "2_3") (pintype "passive"))
      (node (ref "S2") (pin "4") (pinfunction "3_4") (pintype "passive"))
      (node (ref "U1") (pin "12") (pinfunction "GPIO.2_12") (pintype "passive"))
      (node (ref "U3") (pin "38") (pinfunction "~{U1RTS/BCLK1/CN21/RD15}_38") (pintype "bidirectional"))
    )
    (net (code "83") (name "USB_RXD") (class "Default")
      (node (ref "U1") (pin "20") (pinfunction "RXD_20") (pintype "input"))
      (node (ref "U3") (pin "40") (pinfunction "PMA8/U2TX/CN18/RF5_40") (pintype "bidirectional"))
    )
    (net (code "84") (name "USB_TXD") (class "Default")
      (node (ref "U1") (pin "21") (pinfunction "TXD_21") (pintype "output"))
      (node (ref "U3") (pin "39") (pinfunction "PMA9/U2RX/CN17/RF4_39") (pintype "bidirectional"))
    )
    (net (code "85") (name "WIFI_INT_") (class "Default")
      (node (ref "J6") (pin "7") (pinfunction "7_7") (pintype "passive"))
      (node (ref "U3") (pin "13") (pinfunction "TMS/INT1/RE8_13") (pintype "bidirectional"))
    )
    (net (code "86") (name "WIND_COUNT_IN") (class "Default")
      (node (ref "J1") (pin "P$8") (pinfunction "8_P$8") (pintype "bidirectional"))
      (node (ref "R1") (pin "1") (pinfunction "1_1") (pintype "passive"))
    )
    (net (code "87") (name "WIN_DIR_IN") (class "Default")
      (node (ref "J1") (pin "P$4") (pinfunction "4_P$4") (pintype "bidirectional"))
      (node (ref "R5") (pin "1") (pinfunction "1_1") (pintype "passive"))
    )
    (net (code "88") (name "unconnected-(+5V-Pad2)") (class "Default")
      (node (ref "+5V") (pin "2") (pinfunction "2_2") (pintype "passive"))
    )
    (net (code "89") (name "unconnected-(FAN-Pad2)") (class "Default")
      (node (ref "FAN") (pin "2") (pinfunction "2_2") (pintype "passive"))
    )
    (net (code "90") (name "unconnected-(J5-6-PadP$6)") (class "Default")
      (node (ref "J5") (pin "P$6") (pinfunction "6_P$6") (pintype "bidirectional"))
    )
    (net (code "91") (name "unconnected-(J6-Pad1)") (class "Default")
      (node (ref "J6") (pin "1") (pinfunction "1_1") (pintype "passive"))
    )
    (net (code "92") (name "unconnected-(U1-*RST-Pad9)") (class "Default")
      (node (ref "U1") (pin "9") (pinfunction "*RST_9") (pintype "passive"))
    )
    (net (code "93") (name "unconnected-(U1-*SUSPEND-Pad15)") (class "Default")
      (node (ref "U1") (pin "15") (pinfunction "*SUSPEND_15") (pintype "output"))
    )
    (net (code "94") (name "unconnected-(U1-CTS-Pad18)") (class "Default")
      (node (ref "U1") (pin "18") (pinfunction "CTS_18") (pintype "input"))
    )
    (net (code "95") (name "unconnected-(U1-DCD-Pad24)") (class "Default")
      (node (ref "U1") (pin "24") (pinfunction "DCD_24") (pintype "input"))
    )
    (net (code "96") (name "unconnected-(U1-DSR-Pad22)") (class "Default")
      (node (ref "U1") (pin "22") (pinfunction "DSR_22") (pintype "input"))
    )
    (net (code "97") (name "unconnected-(U1-DTR-Pad23)") (class "Default")
      (node (ref "U1") (pin "23") (pinfunction "DTR_23") (pintype "output"))
    )
    (net (code "98") (name "unconnected-(U1-GPIO.3-Pad11)") (class "Default")
      (node (ref "U1") (pin "11") (pinfunction "GPIO.3_11") (pintype "passive"))
    )
    (net (code "99") (name "unconnected-(U1-NC-Pad10)") (class "Default")
      (node (ref "U1") (pin "10") (pinfunction "NC_10") (pintype "no_connect"))
    )
    (net (code "100") (name "unconnected-(U1-RI-Pad1)") (class "Default")
      (node (ref "U1") (pin "1") (pinfunction "RI_1") (pintype "input"))
    )
    (net (code "101") (name "unconnected-(U1-RTS-Pad19)") (class "Default")
      (node (ref "U1") (pin "19") (pinfunction "RTS_19") (pintype "output"))
    )
    (net (code "102") (name "unconnected-(U1-SUSPEND-Pad17)") (class "Default")
      (node (ref "U1") (pin "17") (pinfunction "SUSPEND_17") (pintype "output"))
    )
    (net (code "103") (name "unconnected-(U1-VPP-Pad16)") (class "Default")
      (node (ref "U1") (pin "16") (pinfunction "VPP_16") (pintype "passive"))
    )
    (net (code "104") (name "unconnected-(USB-Pad4_ID)") (class "Default")
      (node (ref "USB") (pin "4_ID") (pinfunction "4_ID_4_ID") (pintype "passive"))
    )
  )
)
